# decoder.net
KiCad netlist of a schematic drawn in EAGLE
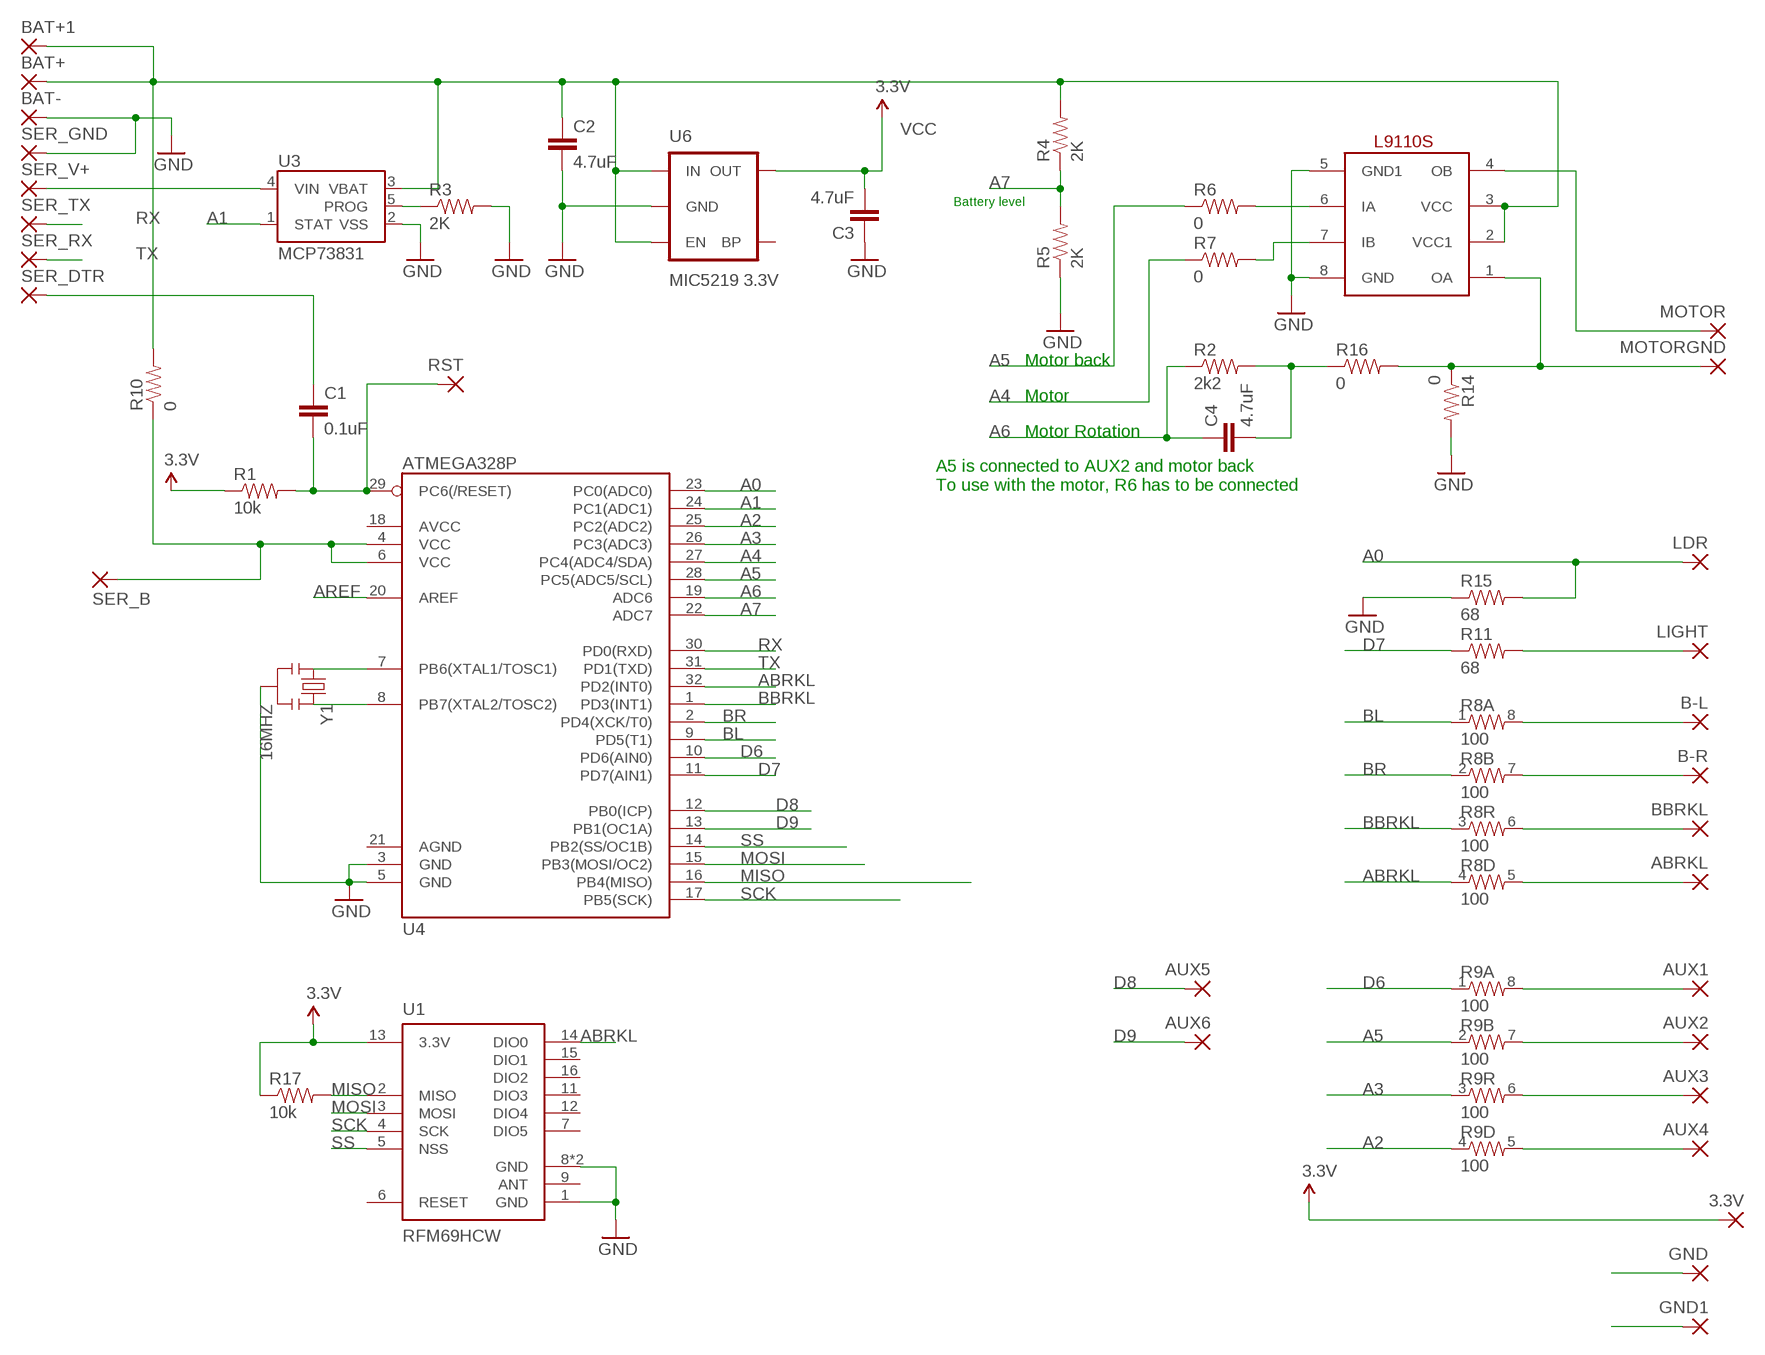
[diagram p0: schematic, sheet 1]

(export (version "E")
  (design (tool "Eeschema 10.0.6"))
  (components
    (comp (ref "3.3V")
      (value "SMD2")
      (footprint "eagle-import:SMD1,27-2,54")
      (libsource (lib "eagle-import") (part "SMD2"))
    )
    (comp (ref "ABRKL")
      (value "SMD2")
      (footprint "eagle-import:SMD1,27-2,54")
      (libsource (lib "eagle-import") (part "SMD2"))
    )
    (comp (ref "AUX1")
      (value "SMD2")
      (footprint "eagle-import:SMD1,27-2,54")
      (libsource (lib "eagle-import") (part "SMD2"))
    )
    (comp (ref "AUX2")
      (value "SMD2")
      (footprint "eagle-import:SMD1,27-2,54")
      (libsource (lib "eagle-import") (part "SMD2"))
    )
    (comp (ref "AUX3")
      (value "SMD2")
      (footprint "eagle-import:SMD1,27-2,54")
      (libsource (lib "eagle-import") (part "SMD2"))
    )
    (comp (ref "AUX4")
      (value "SMD2")
      (footprint "eagle-import:SMD1,27-2,54")
      (libsource (lib "eagle-import") (part "SMD2"))
    )
    (comp (ref "AUX5")
      (value "SMD2")
      (footprint "eagle-import:SMD1,27-2,54")
      (libsource (lib "eagle-import") (part "SMD2"))
    )
    (comp (ref "AUX6")
      (value "SMD2")
      (footprint "eagle-import:SMD1,27-2,54")
      (libsource (lib "eagle-import") (part "SMD2"))
    )
    (comp (ref "B-L")
      (value "SMD2")
      (footprint "eagle-import:SMD1,27-2,54")
      (libsource (lib "eagle-import") (part "SMD2"))
    )
    (comp (ref "B-R")
      (value "SMD2")
      (footprint "eagle-import:SMD1,27-2,54")
      (libsource (lib "eagle-import") (part "SMD2"))
    )
    (comp (ref "BAT+")
      (value "SMD2")
      (footprint "eagle-import:SMD1,27-2,54")
      (libsource (lib "eagle-import") (part "SMD2"))
    )
    (comp (ref "BAT+1")
      (value "SMD2")
      (footprint "eagle-import:SMD1,27-2,54")
      (libsource (lib "eagle-import") (part "SMD2"))
    )
    (comp (ref "BAT-")
      (value "SMD2")
      (footprint "eagle-import:SMD1,27-2,54")
      (libsource (lib "eagle-import") (part "SMD2"))
    )
    (comp (ref "BBRKL")
      (value "SMD2")
      (footprint "eagle-import:SMD1,27-2,54")
      (libsource (lib "eagle-import") (part "SMD2"))
    )
    (comp (ref "C1")
      (value "0.1uF")
      (footprint "eagle-import:0805")
      (libsource (lib "eagle-import") (part "CAP0805"))
    )
    (comp (ref "C2")
      (value "4.7uF")
      (footprint "eagle-import:0805")
      (libsource (lib "eagle-import") (part "CAP0805"))
    )
    (comp (ref "C3")
      (value "4.7uF")
      (footprint "eagle-import:0805")
      (libsource (lib "eagle-import") (part "CAP0805"))
    )
    (comp (ref "C4")
      (value "4.7uF")
      (footprint "eagle-import:0805")
      (libsource (lib "eagle-import") (part "CAP0805"))
    )
    (comp (ref "GND")
      (value "SMD2")
      (footprint "eagle-import:SMD1,27-2,54")
      (libsource (lib "eagle-import") (part "SMD2"))
    )
    (comp (ref "GND1")
      (value "SMD2")
      (footprint "eagle-import:SMD1,27-2,54")
      (libsource (lib "eagle-import") (part "SMD2"))
    )
    (comp (ref "LDR")
      (value "SMD2")
      (footprint "eagle-import:SMD1,27-2,54")
      (libsource (lib "eagle-import") (part "SMD2"))
    )
    (comp (ref "LIGHT")
      (value "SMD2")
      (footprint "eagle-import:SMD1,27-2,54")
      (libsource (lib "eagle-import") (part "SMD2"))
    )
    (comp (ref "MDRIVER")
      (value "L9110S")
      (footprint "eagle-import:SO08")
      (libsource (lib "eagle-import") (part "L9110S"))
    )
    (comp (ref "MOTOR")
      (value "SMD2")
      (footprint "eagle-import:SMD1,27-2,54")
      (libsource (lib "eagle-import") (part "SMD2"))
    )
    (comp (ref "MOTORGND")
      (value "SMD2")
      (footprint "eagle-import:SMD1,27-2,54")
      (libsource (lib "eagle-import") (part "SMD2"))
    )
    (comp (ref "R1")
      (value "10k")
      (footprint "eagle-import:0603-RES")
      (libsource (lib "eagle-import") (part "RESISTOR0603-RES"))
    )
    (comp (ref "R2")
      (value "2k2")
      (footprint "eagle-import:0603-RES")
      (libsource (lib "eagle-import") (part "RESISTOR0603-RES"))
    )
    (comp (ref "R3")
      (value "2K")
      (footprint "eagle-import:0603-RES")
      (libsource (lib "eagle-import") (part "RESISTOR0603-RES"))
    )
    (comp (ref "R4")
      (value "2K")
      (footprint "eagle-import:0603-RES")
      (libsource (lib "eagle-import") (part "RESISTOR0603-RES"))
    )
    (comp (ref "R5")
      (value "2K")
      (footprint "eagle-import:0603-RES")
      (libsource (lib "eagle-import") (part "RESISTOR0603-RES"))
    )
    (comp (ref "R6")
      (value "0")
      (footprint "eagle-import:0603-RES")
      (libsource (lib "eagle-import") (part "RESISTOR0603-RES"))
    )
    (comp (ref "R7")
      (value "0")
      (footprint "eagle-import:0603-RES")
      (libsource (lib "eagle-import") (part "RESISTOR0603-RES"))
    )
    (comp (ref "R8")
      (value "100")
      (footprint "eagle-import:0603-ARV")
      (libsource (lib "eagle-import") (part "RESISTOR-ARRAY0603-ARV"))
    )
    (comp (ref "R9")
      (value "100")
      (footprint "eagle-import:0603-ARV")
      (libsource (lib "eagle-import") (part "RESISTOR-ARRAY0603-ARV"))
    )
    (comp (ref "R10")
      (value "0")
      (footprint "eagle-import:0603-RES")
      (libsource (lib "eagle-import") (part "RESISTOR0603-RES"))
    )
    (comp (ref "R11")
      (value "68")
      (footprint "eagle-import:0603-RES")
      (libsource (lib "eagle-import") (part "RESISTOR0603-RES"))
    )
    (comp (ref "R14")
      (value "0")
      (footprint "eagle-import:0603-RES")
      (libsource (lib "eagle-import") (part "RESISTOR0603-RES"))
    )
    (comp (ref "R15")
      (value "68")
      (footprint "eagle-import:0603-RES")
      (libsource (lib "eagle-import") (part "RESISTOR0603-RES"))
    )
    (comp (ref "R16")
      (value "0")
      (footprint "eagle-import:0603-RES")
      (libsource (lib "eagle-import") (part "RESISTOR0603-RES"))
    )
    (comp (ref "R17")
      (value "10k")
      (footprint "eagle-import:0603-RES")
      (libsource (lib "eagle-import") (part "RESISTOR0603-RES"))
    )
    (comp (ref "RST")
      (value "SMD2")
      (footprint "eagle-import:SMD1,27-2,54")
      (libsource (lib "eagle-import") (part "SMD2"))
    )
    (comp (ref "SER_B")
      (value "SMD2")
      (footprint "eagle-import:SMD1,27-2,54")
      (libsource (lib "eagle-import") (part "SMD2"))
    )
    (comp (ref "SER_DTR")
      (value "SMD2")
      (footprint "eagle-import:SMD1,27-2,54")
      (libsource (lib "eagle-import") (part "SMD2"))
    )
    (comp (ref "SER_GND")
      (value "SMD2")
      (footprint "eagle-import:SMD1,27-2,54")
      (libsource (lib "eagle-import") (part "SMD2"))
    )
    (comp (ref "SER_RX")
      (value "SMD2")
      (footprint "eagle-import:SMD1,27-2,54")
      (libsource (lib "eagle-import") (part "SMD2"))
    )
    (comp (ref "SER_TX")
      (value "SMD2")
      (footprint "eagle-import:SMD1,27-2,54")
      (libsource (lib "eagle-import") (part "SMD2"))
    )
    (comp (ref "SER_V+")
      (value "SMD2")
      (footprint "eagle-import:SMD1,27-2,54")
      (libsource (lib "eagle-import") (part "SMD2"))
    )
    (comp (ref "U1")
      (value "RFM69HCW")
      (footprint "eagle-import:RFM69HCW-XXXS2")
      (libsource (lib "eagle-import") (part "RFM69HCW"))
    )
    (comp (ref "U3")
      (value "MCP73831")
      (footprint "eagle-import:SOT23-5")
      (libsource (lib "eagle-import") (part "MCP73831"))
    )
    (comp (ref "U4")
      (value "ATMEGA328P")
      (footprint "eagle-import:TQFP32-08")
      (libsource (lib "eagle-import") (part "ATMEGA328_SMT"))
    )
    (comp (ref "U6")
      (value "MIC5219 3.3V")
      (footprint "eagle-import:SOT23-5")
      (libsource (lib "eagle-import") (part "V_REG_MIC52193.3V"))
    )
    (comp (ref "Y1")
      (value "16MHZ")
      (footprint "eagle-import:RESONATOR-SMD")
      (libsource (lib "eagle-import") (part "RESONATOR16MHZ"))
    )
  )
  (nets
    (net (code "1") (name "/A0") (class "Default")
      (node (ref "LDR") (pin "1") (pinfunction "P_1") (pintype "passive"))
      (node (ref "R15") (pin "2") (pinfunction "2_2") (pintype "passive"))
      (node (ref "U4") (pin "23") (pinfunction "PC0(ADC0)_23") (pintype "bidirectional"))
    )
    (net (code "2") (name "/A1") (class "Default")
      (node (ref "U3") (pin "1") (pinfunction "STAT_1") (pintype "output"))
      (node (ref "U4") (pin "24") (pinfunction "PC1(ADC1)_24") (pintype "bidirectional"))
    )
    (net (code "3") (name "/A2") (class "Default")
      (node (ref "R9") (pin "4") (pinfunction "1_4") (pintype "passive"))
      (node (ref "U4") (pin "25") (pinfunction "PC2(ADC2)_25") (pintype "bidirectional"))
    )
    (net (code "4") (name "/A3") (class "Default")
      (node (ref "R9") (pin "3") (pinfunction "1_3") (pintype "passive"))
      (node (ref "U4") (pin "26") (pinfunction "PC3(ADC3)_26") (pintype "bidirectional"))
    )
    (net (code "5") (name "/A4") (class "Default")
      (node (ref "R7") (pin "1") (pinfunction "1_1") (pintype "passive"))
      (node (ref "U4") (pin "27") (pinfunction "PC4(ADC4/SDA)_27") (pintype "bidirectional"))
    )
    (net (code "6") (name "/A5") (class "Default")
      (node (ref "R6") (pin "1") (pinfunction "1_1") (pintype "passive"))
      (node (ref "R9") (pin "2") (pinfunction "1_2") (pintype "passive"))
      (node (ref "U4") (pin "28") (pinfunction "PC5(ADC5/SCL)_28") (pintype "bidirectional"))
    )
    (net (code "7") (name "/A6") (class "Default")
      (node (ref "C4") (pin "1") (pinfunction "1_1") (pintype "passive"))
      (node (ref "R2") (pin "1") (pinfunction "1_1") (pintype "passive"))
      (node (ref "U4") (pin "19") (pinfunction "ADC6_19") (pintype "bidirectional"))
    )
    (net (code "8") (name "/A7") (class "Default")
      (node (ref "R4") (pin "1") (pinfunction "1_1") (pintype "passive"))
      (node (ref "R5") (pin "2") (pinfunction "2_2") (pintype "passive"))
      (node (ref "U4") (pin "22") (pinfunction "ADC7_22") (pintype "bidirectional"))
    )
    (net (code "9") (name "/ABRKL") (class "Default")
      (node (ref "R8") (pin "4") (pinfunction "1_4") (pintype "passive"))
      (node (ref "U1") (pin "14") (pinfunction "DIO0_14") (pintype "bidirectional"))
      (node (ref "U4") (pin "32") (pinfunction "PD2(INT0)_32") (pintype "bidirectional"))
    )
    (net (code "10") (name "/AREF") (class "Default")
      (node (ref "U4") (pin "20") (pinfunction "AREF_20") (pintype "bidirectional"))
    )
    (net (code "11") (name "/BBRKL") (class "Default")
      (node (ref "R8") (pin "3") (pinfunction "1_3") (pintype "passive"))
      (node (ref "U4") (pin "1") (pinfunction "PD3(INT1)_1") (pintype "bidirectional"))
    )
    (net (code "12") (name "/BL") (class "Default")
      (node (ref "R8") (pin "1") (pinfunction "1_1") (pintype "passive"))
      (node (ref "U4") (pin "9") (pinfunction "PD5(T1)_9") (pintype "bidirectional"))
    )
    (net (code "13") (name "/BR") (class "Default")
      (node (ref "R8") (pin "2") (pinfunction "1_2") (pintype "passive"))
      (node (ref "U4") (pin "2") (pinfunction "PD4(XCK/T0)_2") (pintype "bidirectional"))
    )
    (net (code "14") (name "/D6") (class "Default")
      (node (ref "R9") (pin "1") (pinfunction "1_1") (pintype "passive"))
      (node (ref "U4") (pin "10") (pinfunction "PD6(AIN0)_10") (pintype "bidirectional"))
    )
    (net (code "15") (name "/D7") (class "Default")
      (node (ref "R11") (pin "1") (pinfunction "1_1") (pintype "passive"))
      (node (ref "U4") (pin "11") (pinfunction "PD7(AIN1)_11") (pintype "bidirectional"))
    )
    (net (code "16") (name "/D8") (class "Default")
      (node (ref "AUX5") (pin "1") (pinfunction "P_1") (pintype "passive"))
      (node (ref "U4") (pin "12") (pinfunction "PB0(ICP)_12") (pintype "bidirectional"))
    )
    (net (code "17") (name "/D9") (class "Default")
      (node (ref "AUX6") (pin "1") (pinfunction "P_1") (pintype "passive"))
      (node (ref "U4") (pin "13") (pinfunction "PB1(OC1A)_13") (pintype "bidirectional"))
    )
    (net (code "18") (name "/MISO") (class "Default")
      (node (ref "R17") (pin "2") (pinfunction "2_2") (pintype "passive"))
      (node (ref "U1") (pin "2") (pinfunction "MISO_2") (pintype "bidirectional"))
      (node (ref "U4") (pin "16") (pinfunction "PB4(MISO)_16") (pintype "bidirectional"))
    )
    (net (code "19") (name "/MOSI") (class "Default")
      (node (ref "U1") (pin "3") (pinfunction "MOSI_3") (pintype "input"))
      (node (ref "U4") (pin "15") (pinfunction "PB3(MOSI/OC2)_15") (pintype "bidirectional"))
    )
    (net (code "20") (name "/RX") (class "Default")
      (node (ref "SER_TX") (pin "1") (pinfunction "P_1") (pintype "passive"))
      (node (ref "U4") (pin "30") (pinfunction "PD0(RXD)_30") (pintype "bidirectional"))
    )
    (net (code "21") (name "/SCK") (class "Default")
      (node (ref "U1") (pin "4") (pinfunction "SCK_4") (pintype "input"))
      (node (ref "U4") (pin "17") (pinfunction "PB5(SCK)_17") (pintype "bidirectional"))
    )
    (net (code "22") (name "/SS") (class "Default")
      (node (ref "U1") (pin "5") (pinfunction "NSS_5") (pintype "input"))
      (node (ref "U4") (pin "14") (pinfunction "PB2(SS/OC1B)_14") (pintype "bidirectional"))
    )
    (net (code "23") (name "/TX") (class "Default")
      (node (ref "SER_RX") (pin "1") (pinfunction "P_1") (pintype "passive"))
      (node (ref "U4") (pin "31") (pinfunction "PD1(TXD)_31") (pintype "bidirectional"))
    )
    (net (code "24") (name "3.3V") (class "Default")
      (node (ref "3.3V") (pin "1") (pinfunction "P_1") (pintype "passive"))
      (node (ref "C3") (pin "2") (pinfunction "2_2") (pintype "passive"))
      (node (ref "R1") (pin "1") (pinfunction "1_1") (pintype "passive"))
      (node (ref "R17") (pin "1") (pinfunction "1_1") (pintype "passive"))
      (node (ref "U1") (pin "13") (pinfunction "3.3V_13") (pintype "power_in"))
      (node (ref "U6") (pin "5") (pinfunction "OUT_5") (pintype "passive"))
    )
    (net (code "25") (name "GND") (class "Default")
      (node (ref "BAT-") (pin "1") (pinfunction "P_1") (pintype "passive"))
      (node (ref "C2") (pin "2") (pinfunction "2_2") (pintype "passive"))
      (node (ref "C3") (pin "1") (pinfunction "1_1") (pintype "passive"))
      (node (ref "GND") (pin "1") (pinfunction "P_1") (pintype "passive"))
      (node (ref "GND1") (pin "1") (pinfunction "P_1") (pintype "passive"))
      (node (ref "MDRIVER") (pin "5") (pinfunction "GND1_5") (pintype "passive"))
      (node (ref "MDRIVER") (pin "8") (pinfunction "GND_8") (pintype "output"))
      (node (ref "R14") (pin "2") (pinfunction "2_2") (pintype "passive"))
      (node (ref "R15") (pin "1") (pinfunction "1_1") (pintype "passive"))
      (node (ref "R3") (pin "2") (pinfunction "2_2") (pintype "passive"))
      (node (ref "R5") (pin "1") (pinfunction "1_1") (pintype "passive"))
      (node (ref "SER_GND") (pin "1") (pinfunction "P_1") (pintype "passive"))
      (node (ref "U1") (pin "1") (pinfunction "GND_1") (pintype "power_in"))
      (node (ref "U1") (pin "10") (pinfunction "GND_10") (pintype "power_in"))
      (node (ref "U1") (pin "8") (pinfunction "GND_8") (pintype "power_in"))
      (node (ref "U3") (pin "2") (pinfunction "VSS_2") (pintype "power_in"))
      (node (ref "U4") (pin "3") (pinfunction "GND_3") (pintype "bidirectional"))
      (node (ref "U4") (pin "5") (pinfunction "GND_5") (pintype "bidirectional"))
      (node (ref "U6") (pin "2") (pinfunction "GND_2") (pintype "input"))
      (node (ref "Y1") (pin "2") (pinfunction "2_2") (pintype "passive"))
    )
    (net (code "26") (name "Net-(ABRKL-P)") (class "Default")
      (node (ref "ABRKL") (pin "1") (pinfunction "P_1") (pintype "passive"))
      (node (ref "R8") (pin "5") (pinfunction "2_5") (pintype "passive"))
    )
    (net (code "27") (name "Net-(AUX1-P)") (class "Default")
      (node (ref "AUX1") (pin "1") (pinfunction "P_1") (pintype "passive"))
      (node (ref "R9") (pin "8") (pinfunction "2_8") (pintype "passive"))
    )
    (net (code "28") (name "Net-(AUX2-P)") (class "Default")
      (node (ref "AUX2") (pin "1") (pinfunction "P_1") (pintype "passive"))
      (node (ref "R9") (pin "7") (pinfunction "2_7") (pintype "passive"))
    )
    (net (code "29") (name "Net-(AUX3-P)") (class "Default")
      (node (ref "AUX3") (pin "1") (pinfunction "P_1") (pintype "passive"))
      (node (ref "R9") (pin "6") (pinfunction "2_6") (pintype "passive"))
    )
    (net (code "30") (name "Net-(AUX4-P)") (class "Default")
      (node (ref "AUX4") (pin "1") (pinfunction "P_1") (pintype "passive"))
      (node (ref "R9") (pin "5") (pinfunction "2_5") (pintype "passive"))
    )
    (net (code "31") (name "Net-(B-L-P)") (class "Default")
      (node (ref "B-L") (pin "1") (pinfunction "P_1") (pintype "passive"))
      (node (ref "R8") (pin "8") (pinfunction "2_8") (pintype "passive"))
    )
    (net (code "32") (name "Net-(B-R-P)") (class "Default")
      (node (ref "B-R") (pin "1") (pinfunction "P_1") (pintype "passive"))
      (node (ref "R8") (pin "7") (pinfunction "2_7") (pintype "passive"))
    )
    (net (code "33") (name "Net-(BAT+-P)") (class "Default")
      (node (ref "BAT+") (pin "1") (pinfunction "P_1") (pintype "passive"))
      (node (ref "BAT+1") (pin "1") (pinfunction "P_1") (pintype "passive"))
      (node (ref "C2") (pin "1") (pinfunction "1_1") (pintype "passive"))
      (node (ref "MDRIVER") (pin "2") (pinfunction "VCC1_2") (pintype "input"))
      (node (ref "MDRIVER") (pin "3") (pinfunction "VCC_3") (pintype "input"))
      (node (ref "R10") (pin "2") (pinfunction "2_2") (pintype "passive"))
      (node (ref "R4") (pin "2") (pinfunction "2_2") (pintype "passive"))
      (node (ref "U3") (pin "3") (pinfunction "VBAT_3") (pintype "power_in"))
      (node (ref "U6") (pin "1") (pinfunction "IN_1") (pintype "input"))
      (node (ref "U6") (pin "3") (pinfunction "EN_3") (pintype "input"))
    )
    (net (code "34") (name "Net-(BBRKL-P)") (class "Default")
      (node (ref "BBRKL") (pin "1") (pinfunction "P_1") (pintype "passive"))
      (node (ref "R8") (pin "6") (pinfunction "2_6") (pintype "passive"))
    )
    (net (code "35") (name "Net-(C4-Pad2)") (class "Default")
      (node (ref "C4") (pin "2") (pinfunction "2_2") (pintype "passive"))
      (node (ref "R16") (pin "1") (pinfunction "1_1") (pintype "passive"))
      (node (ref "R2") (pin "2") (pinfunction "2_2") (pintype "passive"))
    )
    (net (code "36") (name "Net-(LIGHT-P)") (class "Default")
      (node (ref "LIGHT") (pin "1") (pinfunction "P_1") (pintype "passive"))
      (node (ref "R11") (pin "2") (pinfunction "2_2") (pintype "passive"))
    )
    (net (code "37") (name "Net-(MDRIVER-IA)") (class "Default")
      (node (ref "MDRIVER") (pin "6") (pinfunction "IA_6") (pintype "passive"))
      (node (ref "R6") (pin "2") (pinfunction "2_2") (pintype "passive"))
    )
    (net (code "38") (name "Net-(MDRIVER-IB)") (class "Default")
      (node (ref "MDRIVER") (pin "7") (pinfunction "IB_7") (pintype "output"))
      (node (ref "R7") (pin "2") (pinfunction "2_2") (pintype "passive"))
    )
    (net (code "39") (name "Net-(MDRIVER-OA)") (class "Default")
      (node (ref "MDRIVER") (pin "1") (pinfunction "OA_1") (pintype "power_in"))
      (node (ref "MOTORGND") (pin "1") (pinfunction "P_1") (pintype "passive"))
      (node (ref "R14") (pin "1") (pinfunction "1_1") (pintype "passive"))
      (node (ref "R16") (pin "2") (pinfunction "2_2") (pintype "passive"))
    )
    (net (code "40") (name "Net-(MDRIVER-OB)") (class "Default")
      (node (ref "MDRIVER") (pin "4") (pinfunction "OB_4") (pintype "power_in"))
      (node (ref "MOTOR") (pin "1") (pinfunction "P_1") (pintype "passive"))
    )
    (net (code "41") (name "Net-(RST-P)") (class "Default")
      (node (ref "C1") (pin "2") (pinfunction "2_2") (pintype "passive"))
      (node (ref "R1") (pin "2") (pinfunction "2_2") (pintype "passive"))
      (node (ref "RST") (pin "1") (pinfunction "P_1") (pintype "passive"))
      (node (ref "U4") (pin "29") (pinfunction "PC6(/RESET)_29") (pintype "bidirectional"))
    )
    (net (code "42") (name "Net-(SER_B-P)") (class "Default")
      (node (ref "R10") (pin "1") (pinfunction "1_1") (pintype "passive"))
      (node (ref "SER_B") (pin "1") (pinfunction "P_1") (pintype "passive"))
      (node (ref "U4") (pin "4") (pinfunction "VCC_4") (pintype "bidirectional"))
      (node (ref "U4") (pin "6") (pinfunction "VCC_6") (pintype "bidirectional"))
    )
    (net (code "43") (name "Net-(SER_DTR-P)") (class "Default")
      (node (ref "C1") (pin "1") (pinfunction "1_1") (pintype "passive"))
      (node (ref "SER_DTR") (pin "1") (pinfunction "P_1") (pintype "passive"))
    )
    (net (code "44") (name "Net-(SER_V+-P)") (class "Default")
      (node (ref "SER_V+") (pin "1") (pinfunction "P_1") (pintype "passive"))
      (node (ref "U3") (pin "4") (pinfunction "VIN_4") (pintype "power_in"))
    )
    (net (code "45") (name "Net-(U3-PROG)") (class "Default")
      (node (ref "R3") (pin "1") (pinfunction "1_1") (pintype "passive"))
      (node (ref "U3") (pin "5") (pinfunction "PROG_5") (pintype "input"))
    )
    (net (code "46") (name "Net-(U4-PB6(XTAL1{slash}TOSC1))") (class "Default")
      (node (ref "U4") (pin "7") (pinfunction "PB6(XTAL1/TOSC1)_7") (pintype "bidirectional"))
      (node (ref "Y1") (pin "1") (pinfunction "1_1") (pintype "passive"))
    )
    (net (code "47") (name "Net-(U4-PB7(XTAL2{slash}TOSC2))") (class "Default")
      (node (ref "U4") (pin "8") (pinfunction "PB7(XTAL2/TOSC2)_8") (pintype "bidirectional"))
      (node (ref "Y1") (pin "3") (pinfunction "3_3") (pintype "passive"))
    )
    (net (code "48") (name "unconnected-(U1-ANT-Pad9)") (class "Default")
      (node (ref "U1") (pin "9") (pinfunction "ANT_9") (pintype "passive"))
    )
    (net (code "49") (name "unconnected-(U1-DIO1-Pad15)") (class "Default")
      (node (ref "U1") (pin "15") (pinfunction "DIO1_15") (pintype "bidirectional"))
    )
    (net (code "50") (name "unconnected-(U1-DIO2-Pad16)") (class "Default")
      (node (ref "U1") (pin "16") (pinfunction "DIO2_16") (pintype "bidirectional"))
    )
    (net (code "51") (name "unconnected-(U1-DIO3-Pad11)") (class "Default")
      (node (ref "U1") (pin "11") (pinfunction "DIO3_11") (pintype "bidirectional"))
    )
    (net (code "52") (name "unconnected-(U1-DIO4-Pad12)") (class "Default")
      (node (ref "U1") (pin "12") (pinfunction "DIO4_12") (pintype "bidirectional"))
    )
    (net (code "53") (name "unconnected-(U1-DIO5-Pad7)") (class "Default")
      (node (ref "U1") (pin "7") (pinfunction "DIO5_7") (pintype "bidirectional"))
    )
    (net (code "54") (name "unconnected-(U1-RESET-Pad6)") (class "Default")
      (node (ref "U1") (pin "6") (pinfunction "RESET_6") (pintype "input"))
    )
    (net (code "55") (name "unconnected-(U4-AGND-Pad21)") (class "Default")
      (node (ref "U4") (pin "21") (pinfunction "AGND_21") (pintype "bidirectional"))
    )
    (net (code "56") (name "unconnected-(U4-AVCC-Pad18)") (class "Default")
      (node (ref "U4") (pin "18") (pinfunction "AVCC_18") (pintype "bidirectional"))
    )
    (net (code "57") (name "unconnected-(U6-BP-Pad4)") (class "Default")
      (node (ref "U6") (pin "4") (pinfunction "BP_4") (pintype "input"))
    )
  )
)
